# CH32V006K8U6-R0-1v0.net
KiCad netlist of a schematic drawn in Altium Designer
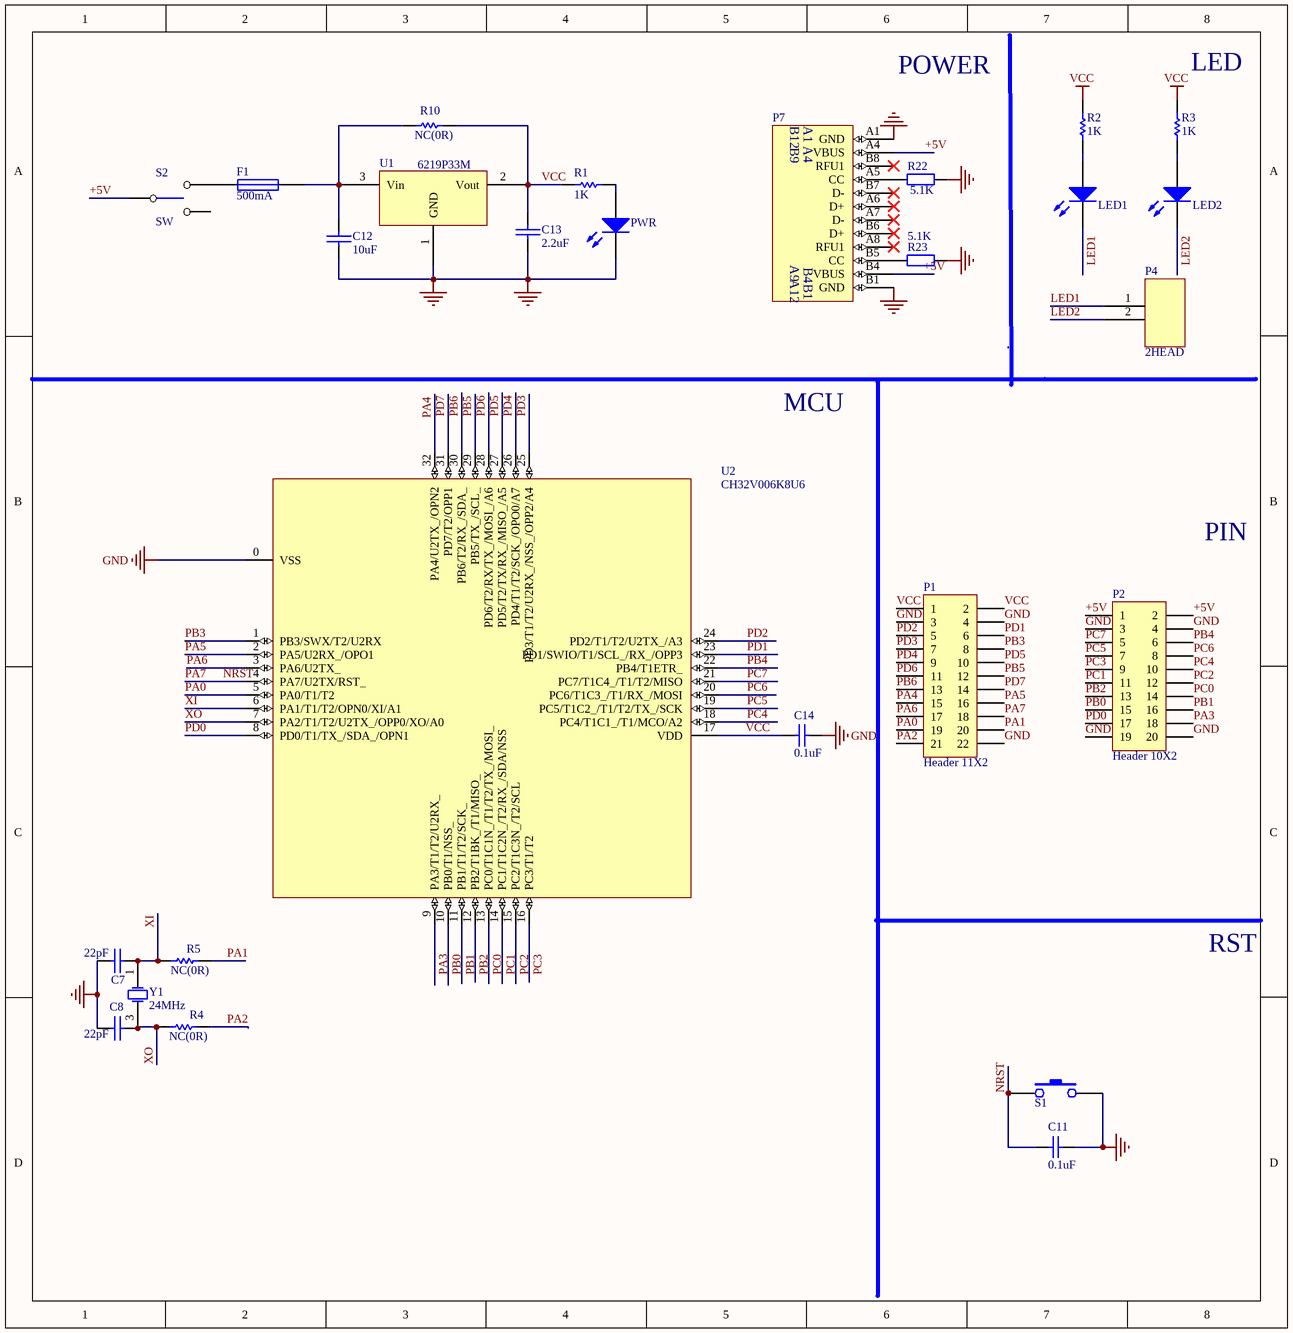
[diagram p0: CH32V006K8U6-R0-1v0.SchDoc]

(export (version "E")
  (design (tool "Eeschema 10.0.6"))
  (components
    (comp (ref "C7")
      (value "22pF")
      (footprint "0402_C")
      (description "Capacitor")
      (libsource (lib "*") (part "CAP"))
    )
    (comp (ref "C8")
      (value "22pF")
      (footprint "0402_C")
      (description "Capacitor")
      (libsource (lib "*") (part "CAP"))
    )
    (comp (ref "C11")
      (value "0.1uF")
      (footprint "0402_C")
      (description "Capacitor")
      (fields (field (name "PUBLISHER") "Altium Limited"))
      (libsource (lib "*") (part "Cap"))
    )
    (comp (ref "C12")
      (value "10uF")
      (footprint "0603_C")
      (description "Capacitor")
      (libsource (lib "wch_sch_others") (part "CAP"))
    )
    (comp (ref "C13")
      (value "2.2uF")
      (footprint "0402_C")
      (description "Capacitor")
      (libsource (lib "wch_sch_others") (part "CAP"))
    )
    (comp (ref "C14")
      (value "0.1uF")
      (footprint "0402_C")
      (description "Capacitor")
      (fields (field (name "PUBLISHER") "Altium Limited"))
      (libsource (lib "*") (part "Cap"))
    )
    (comp (ref "F1")
      (value "500mA")
      (footprint "0603")
      (description "Fuse")
      (libsource (lib "*") (part "FUSE1"))
    )
    (comp (ref "LED1")
      (value "LED1   blue")
      (footprint "0603+")
      (description "Typical INFRARED GaAs LED")
      (fields (field (name "PUBLISHER") "Altium Limited"))
      (libsource (lib "") (part "LED0_1"))
    )
    (comp (ref "LED2")
      (value "LED2  blue")
      (footprint "0603+")
      (description "Typical INFRARED GaAs LED")
      (fields (field (name "PUBLISHER") "Altium Limited"))
      (libsource (lib "") (part "LED0_1"))
    )
    (comp (ref "P1")
      (value "Header 11X2")
      (footprint "IDC22-2.54mm")
      (description "Header, 11-Pin, Dual row")
      (fields (field (name "PUBLISHER") "Altium Limited"))
      (libsource (lib "Miscellaneous Connectors") (part "Header 11X2"))
    )
    (comp (ref "P2")
      (value "Header 10X2")
      (footprint "IDC20-2.54mm")
      (description "Header, 10-Pin, Dual row")
      (fields (field (name "PUBLISHER") "Altium Limited"))
      (libsource (lib "Miscellaneous Connectors") (part "Header 10X2"))
    )
    (comp (ref "P4") (value "2HEAD") (footprint "SIP2-2.54mm") (libsource (lib "*") (part "2HEAD")))
    (comp (ref "P7")
      (value "TYPE-C")
      (footprint "TYPE-C-Receptacle-2.0")
      (libsource (lib "*") (part "TYPE-C1"))
    )
    (comp (ref "PWR")
      (value "POWER  red")
      (footprint "0603+")
      (description "Typical INFRARED GaAs LED")
      (fields (field (name "PUBLISHER") "Altium Limited"))
      (libsource (lib "*") (part "LED0"))
    )
    (comp (ref "R1")
      (value "1K")
      (footprint "0402")
      (description "Semiconductor Resistor")
      (fields (field (name "PUBLISHER") "Altium Limited"))
      (libsource (lib "*") (part "Res Semi"))
    )
    (comp (ref "R2")
      (value "1K")
      (footprint "0402")
      (description "Semiconductor Resistor")
      (fields (field (name "PUBLISHER") "Altium Limited"))
      (libsource (lib "*") (part "Res Semi"))
    )
    (comp (ref "R3")
      (value "1K")
      (footprint "0402")
      (description "Semiconductor Resistor")
      (fields (field (name "PUBLISHER") "Altium Limited"))
      (libsource (lib "*") (part "Res Semi"))
    )
    (comp (ref "R4")
      (value "NC(0R)")
      (footprint "0402")
      (description "Semiconductor Resistor")
      (fields (field (name "Comment") "0R") (field (name "PUBLISHER") "Altium Limited"))
      (libsource (lib "*") (part "Res Semi"))
    )
    (comp (ref "R5")
      (value "NC(0R)")
      (footprint "0402")
      (description "Semiconductor Resistor")
      (fields (field (name "Comment") "0R") (field (name "PUBLISHER") "Altium Limited"))
      (libsource (lib "*") (part "Res Semi"))
    )
    (comp (ref "R10")
      (value "NC(0R)")
      (footprint "0402")
      (description "Semiconductor Resistor")
      (fields (field (name "Comment") "0R") (field (name "PUBLISHER") "Altium Limited"))
      (libsource (lib "*") (part "Res Semi"))
    )
    (comp (ref "R22")
      (value "5.1K")
      (footprint "0402")
      (description "Resistor")
      (libsource (lib "Miscellaneous Devices") (part "Res2"))
    )
    (comp (ref "R23")
      (value "5.1K")
      (footprint "0402")
      (description "Resistor")
      (libsource (lib "Miscellaneous Devices") (part "Res2"))
    )
    (comp (ref "S1") (value "NRST") (footprint "SMD_6.1x3.65x2.5mm-KEY") (libsource (lib "*") (part "KEY")))
    (comp (ref "S2") (value "SW") (footprint "SW1") (libsource (lib "*") (part "SW")))
    (comp (ref "U1")
      (value "6219P33M")
      (footprint "SOT-23")
      (libsource (lib "wch_sch_others") (part "6219P33M"))
    )
    (comp (ref "U2")
      (value "CH32V006K8U6")
      (footprint "QFN32_4X4")
      (description "RISC-V MCU, 48MHz, ADC/OPA/2*UART/I2C/SPI")
      (libsource (lib "DHXXXSCH") (part "CH32V006K8U6"))
    )
    (comp (ref "Y1")
      (value "24MHz")
      (footprint "XT3225")
      (description "Crystal Oscillator")
      (fields (field (name "PUBLISHER") "Altium Limited"))
      (libsource (lib "*") (part "XTAL"))
    )
  )
  (nets
    (net (code "1") (name "/+5V") (class "Default")
      (node (ref "P2") (pin "1") (pinfunction "1_1") (pintype "passive"))
      (node (ref "P2") (pin "2") (pinfunction "2_2") (pintype "passive"))
      (node (ref "P7") (pin "A4") (pinfunction "VBUS_A4") (pintype "bidirectional"))
      (node (ref "P7") (pin "B4") (pinfunction "VBUS_B4") (pintype "bidirectional"))
      (node (ref "S2") (pin "1") (pinfunction "1_1") (pintype "passive"))
    )
    (net (code "2") (name "/LED1") (class "Default")
      (node (ref "LED1") (pin "2") (pinfunction "K_2") (pintype "passive"))
      (node (ref "P4") (pin "1") (pintype "passive"))
    )
    (net (code "3") (name "/LED2") (class "Default")
      (node (ref "LED2") (pin "2") (pinfunction "K_2") (pintype "passive"))
      (node (ref "P4") (pin "2") (pintype "passive"))
    )
    (net (code "4") (name "/NRST") (class "Default")
      (node (ref "C11") (pin "2") (pinfunction "2_2") (pintype "passive"))
      (node (ref "P1") (pin "18") (pinfunction "18_18") (pintype "passive"))
      (node (ref "S1") (pin "1") (pinfunction "1_1") (pintype "passive"))
      (node (ref "U2") (pin "4") (pinfunction "PA7/U2TX/RST__4") (pintype "bidirectional"))
    )
    (net (code "5") (name "/PA0") (class "Default")
      (node (ref "P1") (pin "19") (pinfunction "19_19") (pintype "passive"))
      (node (ref "U2") (pin "5") (pinfunction "PA0/T1/T2_5") (pintype "bidirectional"))
    )
    (net (code "6") (name "/PA1") (class "Default")
      (node (ref "P1") (pin "20") (pinfunction "20_20") (pintype "passive"))
      (node (ref "R5") (pin "2") (pinfunction "2_2") (pintype "passive"))
    )
    (net (code "7") (name "/PA2") (class "Default")
      (node (ref "P1") (pin "21") (pinfunction "21_21") (pintype "passive"))
      (node (ref "R4") (pin "2") (pinfunction "2_2") (pintype "passive"))
    )
    (net (code "8") (name "/PA3") (class "Default")
      (node (ref "P2") (pin "18") (pinfunction "18_18") (pintype "passive"))
      (node (ref "U2") (pin "9") (pinfunction "PA3/T1/T2/U2RX__9") (pintype "bidirectional"))
    )
    (net (code "9") (name "/PA4") (class "Default")
      (node (ref "P1") (pin "15") (pinfunction "15_15") (pintype "passive"))
      (node (ref "U2") (pin "32") (pinfunction "PA4/U2TX_/OPN2_32") (pintype "bidirectional"))
    )
    (net (code "10") (name "/PA5") (class "Default")
      (node (ref "P1") (pin "16") (pinfunction "16_16") (pintype "passive"))
      (node (ref "U2") (pin "2") (pinfunction "PA5/U2RX_/OPO1_2") (pintype "bidirectional"))
    )
    (net (code "11") (name "/PA6") (class "Default")
      (node (ref "P1") (pin "17") (pinfunction "17_17") (pintype "passive"))
      (node (ref "U2") (pin "3") (pinfunction "PA6/U2TX__3") (pintype "bidirectional"))
    )
    (net (code "12") (name "/PB0") (class "Default")
      (node (ref "P2") (pin "15") (pinfunction "15_15") (pintype "passive"))
      (node (ref "U2") (pin "10") (pinfunction "PB0/T1/NSS__10") (pintype "bidirectional"))
    )
    (net (code "13") (name "/PB1") (class "Default")
      (node (ref "P2") (pin "16") (pinfunction "16_16") (pintype "passive"))
      (node (ref "U2") (pin "11") (pinfunction "PB1/T1/T2/SCK__11") (pintype "bidirectional"))
    )
    (net (code "14") (name "/PB2") (class "Default")
      (node (ref "P2") (pin "13") (pinfunction "13_13") (pintype "passive"))
      (node (ref "U2") (pin "12") (pinfunction "PB2/T1BK_/T1/MISO__12") (pintype "bidirectional"))
    )
    (net (code "15") (name "/PB3") (class "Default")
      (node (ref "P1") (pin "8") (pinfunction "8_8") (pintype "passive"))
      (node (ref "U2") (pin "1") (pinfunction "PB3/SWX/T2/U2RX_1") (pintype "bidirectional"))
    )
    (net (code "16") (name "/PB4") (class "Default")
      (node (ref "P2") (pin "6") (pinfunction "6_6") (pintype "passive"))
      (node (ref "U2") (pin "22") (pinfunction "PB4/T1ETR__22") (pintype "bidirectional"))
    )
    (net (code "17") (name "/PB5") (class "Default")
      (node (ref "P1") (pin "12") (pinfunction "12_12") (pintype "passive"))
      (node (ref "U2") (pin "29") (pinfunction "PB5/TX_/SCL__29") (pintype "bidirectional"))
    )
    (net (code "18") (name "/PB6") (class "Default")
      (node (ref "P1") (pin "13") (pinfunction "13_13") (pintype "passive"))
      (node (ref "U2") (pin "30") (pinfunction "PB6/T2/RX_/SDA__30") (pintype "bidirectional"))
    )
    (net (code "19") (name "/PC0") (class "Default")
      (node (ref "P2") (pin "14") (pinfunction "14_14") (pintype "passive"))
      (node (ref "U2") (pin "13") (pinfunction "PC0/T1C1N_/T1/T2/TX_/MOSI__13") (pintype "bidirectional"))
    )
    (net (code "20") (name "/PC1") (class "Default")
      (node (ref "P2") (pin "11") (pinfunction "11_11") (pintype "passive"))
      (node (ref "U2") (pin "14") (pinfunction "PC1/T1C2N_/T2/RX_/SDA/NSS_14") (pintype "bidirectional"))
    )
    (net (code "21") (name "/PC2") (class "Default")
      (node (ref "P2") (pin "12") (pinfunction "12_12") (pintype "passive"))
      (node (ref "U2") (pin "15") (pinfunction "PC2/T1C3N_/T2/SCL_15") (pintype "bidirectional"))
    )
    (net (code "22") (name "/PC3") (class "Default")
      (node (ref "P2") (pin "9") (pinfunction "9_9") (pintype "passive"))
      (node (ref "U2") (pin "16") (pinfunction "PC3/T1/T2_16") (pintype "bidirectional"))
    )
    (net (code "23") (name "/PC4") (class "Default")
      (node (ref "P2") (pin "10") (pinfunction "10_10") (pintype "passive"))
      (node (ref "U2") (pin "18") (pinfunction "PC4/T1C1_/T1/MCO/A2_18") (pintype "bidirectional"))
    )
    (net (code "24") (name "/PC5") (class "Default")
      (node (ref "P2") (pin "7") (pinfunction "7_7") (pintype "passive"))
      (node (ref "U2") (pin "19") (pinfunction "PC5/T1C2_/T1/T2/TX_/SCK_19") (pintype "bidirectional"))
    )
    (net (code "25") (name "/PC6") (class "Default")
      (node (ref "P2") (pin "8") (pinfunction "8_8") (pintype "passive"))
      (node (ref "U2") (pin "20") (pinfunction "PC6/T1C3_/T1/RX_/MOSI_20") (pintype "bidirectional"))
    )
    (net (code "26") (name "/PC7") (class "Default")
      (node (ref "P2") (pin "5") (pinfunction "5_5") (pintype "passive"))
      (node (ref "U2") (pin "21") (pinfunction "PC7/T1C4_/T1/T2/MISO_21") (pintype "bidirectional"))
    )
    (net (code "27") (name "/PD0") (class "Default")
      (node (ref "P2") (pin "17") (pinfunction "17_17") (pintype "passive"))
      (node (ref "U2") (pin "8") (pinfunction "PD0/T1/TX_/SDA_/OPN1_8") (pintype "bidirectional"))
    )
    (net (code "28") (name "/PD1") (class "Default")
      (node (ref "P1") (pin "6") (pinfunction "6_6") (pintype "passive"))
      (node (ref "U2") (pin "23") (pinfunction "PD1/SWIO/T1/SCL_/RX_/OPP3_23") (pintype "bidirectional"))
    )
    (net (code "29") (name "/PD2") (class "Default")
      (node (ref "P1") (pin "5") (pinfunction "5_5") (pintype "passive"))
      (node (ref "U2") (pin "24") (pinfunction "PD2/T1/T2/U2TX_/A3_24") (pintype "bidirectional"))
    )
    (net (code "30") (name "/PD3") (class "Default")
      (node (ref "P1") (pin "7") (pinfunction "7_7") (pintype "passive"))
      (node (ref "U2") (pin "25") (pinfunction "PD3/T1/T2/U2RX_/NSS_/OPP2/A4_25") (pintype "bidirectional"))
    )
    (net (code "31") (name "/PD4") (class "Default")
      (node (ref "P1") (pin "9") (pinfunction "9_9") (pintype "passive"))
      (node (ref "U2") (pin "26") (pinfunction "PD4/T1/T2/SCK_/OPO0/A7_26") (pintype "bidirectional"))
    )
    (net (code "32") (name "/PD5") (class "Default")
      (node (ref "P1") (pin "10") (pinfunction "10_10") (pintype "passive"))
      (node (ref "U2") (pin "27") (pinfunction "PD5/T2/TX/RX_/MISO_/A5_27") (pintype "bidirectional"))
    )
    (net (code "33") (name "/PD6") (class "Default")
      (node (ref "P1") (pin "11") (pinfunction "11_11") (pintype "passive"))
      (node (ref "U2") (pin "28") (pinfunction "PD6/T2/RX/TX_/MOSI_/A6_28") (pintype "bidirectional"))
    )
    (net (code "34") (name "/PD7") (class "Default")
      (node (ref "P1") (pin "14") (pinfunction "14_14") (pintype "passive"))
      (node (ref "U2") (pin "31") (pinfunction "PD7/T2/OPP1_31") (pintype "bidirectional"))
    )
    (net (code "35") (name "/XI") (class "Default")
      (node (ref "C7") (pin "2") (pinfunction "2_2") (pintype "passive"))
      (node (ref "R5") (pin "1") (pinfunction "1_1") (pintype "passive"))
      (node (ref "U2") (pin "6") (pinfunction "PA1/T1/T2/OPN0/XI/A1_6") (pintype "bidirectional"))
      (node (ref "Y1") (pin "1") (pinfunction "OSC1_1") (pintype "passive"))
    )
    (net (code "36") (name "/XO") (class "Default")
      (node (ref "C8") (pin "2") (pinfunction "2_2") (pintype "passive"))
      (node (ref "R4") (pin "1") (pinfunction "1_1") (pintype "passive"))
      (node (ref "U2") (pin "7") (pinfunction "PA2/T1/T2/U2TX_/OPP0/XO/A0_7") (pintype "bidirectional"))
      (node (ref "Y1") (pin "3") (pinfunction "OSC2_3") (pintype "passive"))
    )
    (net (code "37") (name "GND") (class "Default")
      (node (ref "C11") (pin "1") (pinfunction "1_1") (pintype "passive"))
      (node (ref "C12") (pin "2") (pinfunction "2_2") (pintype "passive"))
      (node (ref "C13") (pin "1") (pinfunction "1_1") (pintype "passive"))
      (node (ref "C14") (pin "2") (pinfunction "2_2") (pintype "passive"))
      (node (ref "C7") (pin "1") (pinfunction "1_1") (pintype "passive"))
      (node (ref "C8") (pin "1") (pinfunction "1_1") (pintype "passive"))
      (node (ref "P1") (pin "22") (pinfunction "22_22") (pintype "passive"))
      (node (ref "P1") (pin "3") (pinfunction "3_3") (pintype "passive"))
      (node (ref "P1") (pin "4") (pinfunction "4_4") (pintype "passive"))
      (node (ref "P2") (pin "19") (pinfunction "19_19") (pintype "passive"))
      (node (ref "P2") (pin "20") (pinfunction "20_20") (pintype "passive"))
      (node (ref "P2") (pin "3") (pinfunction "3_3") (pintype "passive"))
      (node (ref "P2") (pin "4") (pinfunction "4_4") (pintype "passive"))
      (node (ref "P7") (pin "A1") (pinfunction "GND_A1") (pintype "bidirectional"))
      (node (ref "P7") (pin "B1") (pinfunction "GND_B1") (pintype "bidirectional"))
      (node (ref "PWR") (pin "2") (pinfunction "K_2") (pintype "passive"))
      (node (ref "R22") (pin "2") (pinfunction "2_2") (pintype "passive"))
      (node (ref "R23") (pin "2") (pinfunction "2_2") (pintype "passive"))
      (node (ref "S1") (pin "2") (pinfunction "2_2") (pintype "passive"))
      (node (ref "U1") (pin "1") (pinfunction "GND_1") (pintype "passive"))
      (node (ref "U2") (pin "0") (pinfunction "VSS_0") (pintype "power_in"))
    )
    (net (code "38") (name "Net-(F1-Pad1)") (class "Default")
      (node (ref "F1") (pin "1") (pinfunction "1_1") (pintype "passive"))
      (node (ref "S2") (pin "3") (pinfunction "3_3") (pintype "passive"))
    )
    (net (code "39") (name "Net-(LED1-A)") (class "Default")
      (node (ref "LED1") (pin "1") (pinfunction "A_1") (pintype "passive"))
      (node (ref "R2") (pin "2") (pinfunction "2_2") (pintype "passive"))
    )
    (net (code "40") (name "Net-(LED2-A)") (class "Default")
      (node (ref "LED2") (pin "1") (pinfunction "A_1") (pintype "passive"))
      (node (ref "R3") (pin "2") (pinfunction "2_2") (pintype "passive"))
    )
    (net (code "41") (name "Net-(P7-CC-PadA5)") (class "Default")
      (node (ref "P7") (pin "A5") (pinfunction "CC_A5") (pintype "bidirectional"))
      (node (ref "R22") (pin "1") (pinfunction "1_1") (pintype "passive"))
    )
    (net (code "42") (name "Net-(P7-CC-PadB5)") (class "Default")
      (node (ref "P7") (pin "B5") (pinfunction "CC_B5") (pintype "bidirectional"))
      (node (ref "R23") (pin "1") (pinfunction "1_1") (pintype "passive"))
    )
    (net (code "43") (name "Net-(PWR-A)") (class "Default")
      (node (ref "PWR") (pin "1") (pinfunction "A_1") (pintype "passive"))
      (node (ref "R1") (pin "1") (pinfunction "1_1") (pintype "passive"))
    )
    (net (code "44") (name "Net-(U1-Vin)") (class "Default")
      (node (ref "C12") (pin "1") (pinfunction "1_1") (pintype "passive"))
      (node (ref "F1") (pin "2") (pinfunction "2_2") (pintype "passive"))
      (node (ref "R10") (pin "1") (pinfunction "1_1") (pintype "passive"))
      (node (ref "U1") (pin "3") (pinfunction "Vin_3") (pintype "passive"))
    )
    (net (code "45") (name "VCC") (class "Default")
      (node (ref "C13") (pin "2") (pinfunction "2_2") (pintype "passive"))
      (node (ref "C14") (pin "1") (pinfunction "1_1") (pintype "passive"))
      (node (ref "P1") (pin "1") (pinfunction "1_1") (pintype "passive"))
      (node (ref "P1") (pin "2") (pinfunction "2_2") (pintype "passive"))
      (node (ref "R1") (pin "2") (pinfunction "2_2") (pintype "passive"))
      (node (ref "R10") (pin "2") (pinfunction "2_2") (pintype "passive"))
      (node (ref "R2") (pin "1") (pinfunction "1_1") (pintype "passive"))
      (node (ref "R3") (pin "1") (pinfunction "1_1") (pintype "passive"))
      (node (ref "U1") (pin "2") (pinfunction "Vout_2") (pintype "passive"))
      (node (ref "U2") (pin "17") (pinfunction "VDD_17") (pintype "power_in"))
    )
    (net (code "46") (name "unconnected-(P7-D+-PadA6)") (class "Default")
      (node (ref "P7") (pin "A6") (pinfunction "D+_A6") (pintype "bidirectional+no_connect"))
    )
    (net (code "47") (name "unconnected-(P7-D+-PadB6)") (class "Default")
      (node (ref "P7") (pin "B6") (pinfunction "D+_B6") (pintype "bidirectional+no_connect"))
    )
    (net (code "48") (name "unconnected-(P7-D--PadA7)") (class "Default")
      (node (ref "P7") (pin "A7") (pinfunction "D-_A7") (pintype "bidirectional+no_connect"))
    )
    (net (code "49") (name "unconnected-(P7-D--PadB7)") (class "Default")
      (node (ref "P7") (pin "B7") (pinfunction "D-_B7") (pintype "bidirectional+no_connect"))
    )
    (net (code "50") (name "unconnected-(P7-RFU1-PadA8)") (class "Default")
      (node (ref "P7") (pin "A8") (pinfunction "RFU1_A8") (pintype "bidirectional+no_connect"))
    )
    (net (code "51") (name "unconnected-(P7-RFU1-PadB8)") (class "Default")
      (node (ref "P7") (pin "B8") (pinfunction "RFU1_B8") (pintype "bidirectional+no_connect"))
    )
    (net (code "52") (name "unconnected-(S2-Pad2)") (class "Default")
      (node (ref "S2") (pin "2") (pinfunction "2_2") (pintype "passive"))
    )
  )
)
